# Ethernet_Connector.net
KiCad netlist of a schematic drawn in Altium Designer
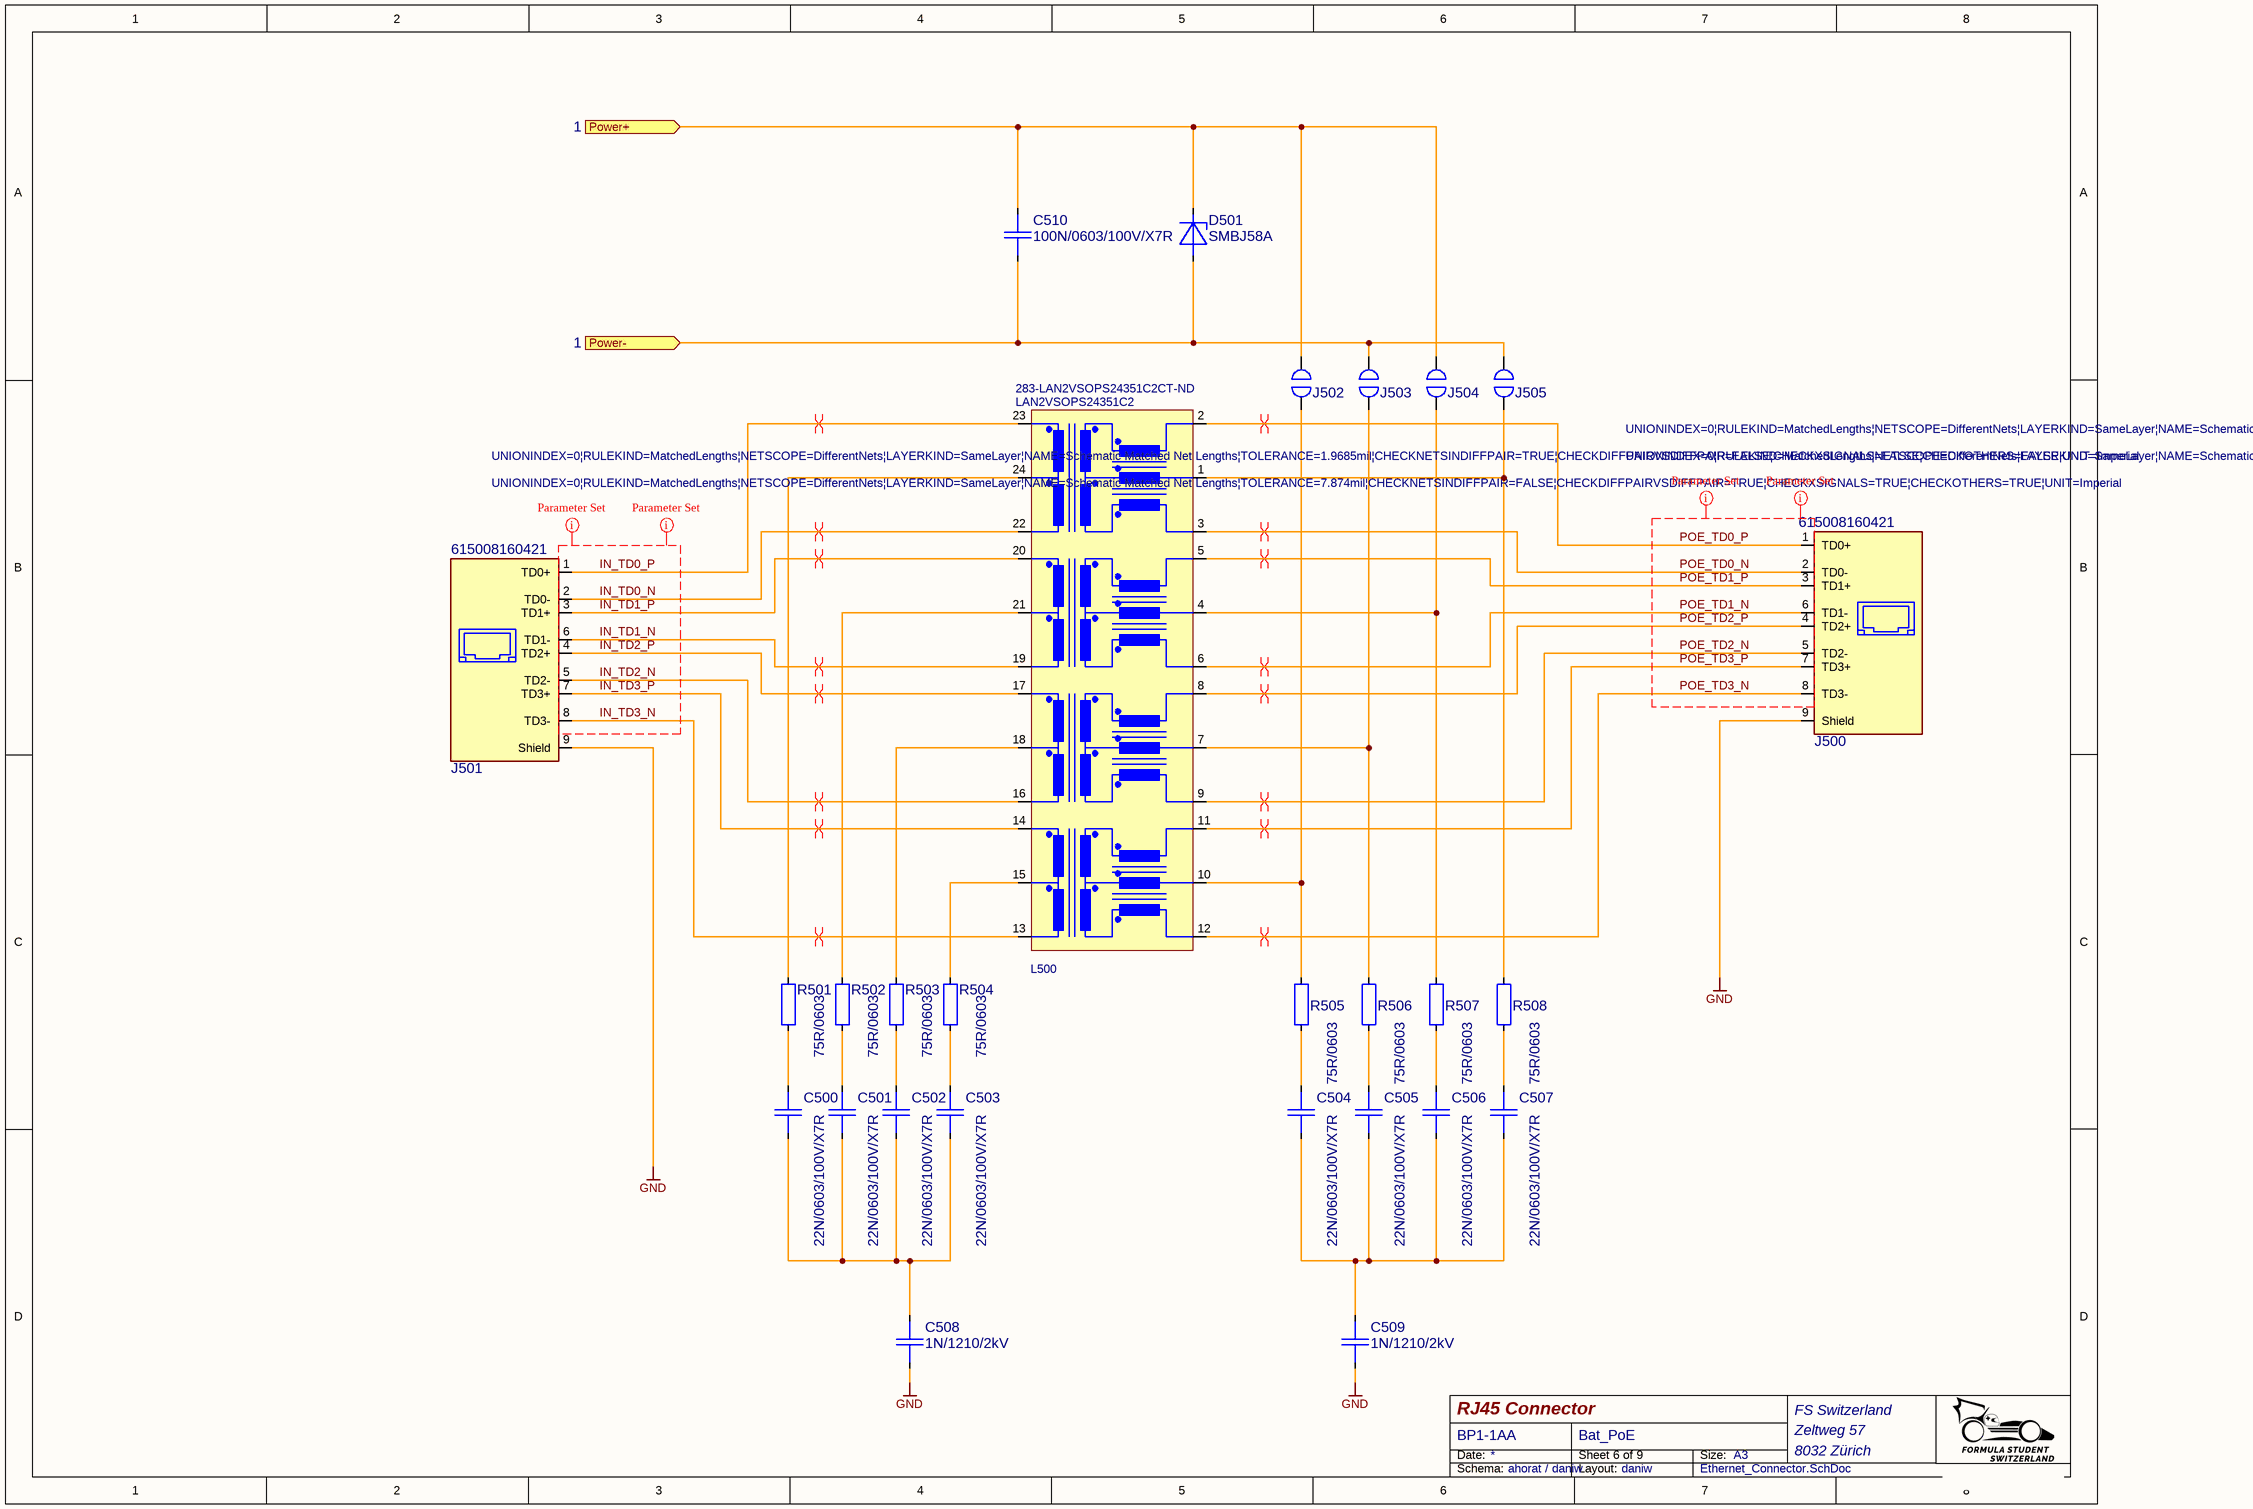
[diagram p0: Ethernet_Connector.SchDoc]

(export (version "E")
  (design (tool "Eeschema 10.0.6"))
  (components
    (comp (ref "C500")
      (value "22N/0603/100V/X7R")
      (footprint "CAP0603_X7R")
      (description "CAP SM 0603 22nF 100V X7R")
      (fields (field (name "MANUFACTURER") "GENERIC"))
      (libsource (lib "daniw_altium_lib") (part "C"))
    )
    (comp (ref "C501")
      (value "22N/0603/100V/X7R")
      (footprint "CAP0603_X7R")
      (description "CAP SM 0603 22nF 100V X7R")
      (fields (field (name "MANUFACTURER") "GENERIC"))
      (libsource (lib "daniw_altium_lib") (part "C"))
    )
    (comp (ref "C502")
      (value "22N/0603/100V/X7R")
      (footprint "CAP0603_X7R")
      (description "CAP SM 0603 22nF 100V X7R")
      (fields (field (name "MANUFACTURER") "GENERIC"))
      (libsource (lib "daniw_altium_lib") (part "C"))
    )
    (comp (ref "C503")
      (value "22N/0603/100V/X7R")
      (footprint "CAP0603_X7R")
      (description "CAP SM 0603 22nF 100V X7R")
      (fields (field (name "MANUFACTURER") "GENERIC"))
      (libsource (lib "daniw_altium_lib") (part "C"))
    )
    (comp (ref "C504")
      (value "22N/0603/100V/X7R")
      (footprint "CAP0603_X7R")
      (description "CAP SM 0603 22nF 100V X7R")
      (fields (field (name "MANUFACTURER") "GENERIC"))
      (libsource (lib "daniw_altium_lib") (part "C"))
    )
    (comp (ref "C505")
      (value "22N/0603/100V/X7R")
      (footprint "CAP0603_X7R")
      (description "CAP SM 0603 22nF 100V X7R")
      (fields (field (name "MANUFACTURER") "GENERIC"))
      (libsource (lib "daniw_altium_lib") (part "C"))
    )
    (comp (ref "C506")
      (value "22N/0603/100V/X7R")
      (footprint "CAP0603_X7R")
      (description "CAP SM 0603 22nF 100V X7R")
      (fields (field (name "MANUFACTURER") "GENERIC"))
      (libsource (lib "daniw_altium_lib") (part "C"))
    )
    (comp (ref "C507")
      (value "22N/0603/100V/X7R")
      (footprint "CAP0603_X7R")
      (description "CAP SM 0603 22nF 100V X7R")
      (fields (field (name "MANUFACTURER") "GENERIC"))
      (libsource (lib "daniw_altium_lib") (part "C"))
    )
    (comp (ref "C508")
      (value "1N/1210/2kV")
      (footprint "CAP1210_X7R")
      (description "CAP SM 1210 1nF 2kV")
      (fields (field (name "MANUFACTURER") "GENERIC"))
      (libsource (lib "daniw_altium_lib") (part "C"))
    )
    (comp (ref "C509")
      (value "1N/1210/2kV")
      (footprint "CAP1210_X7R")
      (description "CAP SM 1210 1nF 2kV")
      (fields (field (name "MANUFACTURER") "GENERIC"))
      (libsource (lib "daniw_altium_lib") (part "C"))
    )
    (comp (ref "C510")
      (value "100N/0603/100V/X7R")
      (footprint "CAP0603_X7R")
      (description "CAP SM 0603 100nF 100V X7R")
      (fields (field (name "MANUFACTURER") "GENERIC"))
      (libsource (lib "daniw_altium_lib") (part "C"))
    )
    (comp (ref "D501")
      (value "SMBJ58A")
      (footprint "DIOM5436X265")
      (description "TVS DIODE 58VWM 93.6VC DO214AA")
      (fields (field (name "MANUFACTURER") "Littelfuse Inc."))
      (libsource (lib "daniw_altium_lib") (part "D_Zener"))
    )
    (comp (ref "J500")
      (value "615008160421")
      (footprint "ETH_615008160421")
      (description "CONN MOD JACK 8P8C VERT SHIELDED")
      (fields (field (name "PART NUMBER") "ETH_THT_Vert_Schielded") (field (name "MANUFACTURER") "GENERIC"))
      (libsource (lib "daniw_altium_lib") (part "RJ-45 ETH W/O LED"))
    )
    (comp (ref "J501")
      (value "615008160421")
      (footprint "ETH_615008160421")
      (description "CONN MOD JACK 8P8C VERT SHIELDED")
      (fields (field (name "PART NUMBER") "ETH_THT_Vert_Schielded") (field (name "MANUFACTURER") "GENERIC"))
      (libsource (lib "") (part "RJ-45 ETH W/O LED_1"))
    )
    (comp (ref "J502")
      (value "Solder Jumper 2pin 0.2mm small")
      (footprint "Solder_Jumper_2pin_0.2mm_small")
      (description "Solder jumper with two pins with a spacing of 0.2mm")
      (fields
        (field (name "PART NUMBER") "Solder_Jumper_2pin_0.2mm_small")
        (field (name "MANUFACTURER") "NONE")
      )
      (libsource (lib "daniw_altium_lib") (part "SolderJumper_2"))
    )
    (comp (ref "J503")
      (value "Solder Jumper 2pin 0.2mm small")
      (footprint "Solder_Jumper_2pin_0.2mm_small")
      (description "Solder jumper with two pins with a spacing of 0.2mm")
      (fields
        (field (name "PART NUMBER") "Solder_Jumper_2pin_0.2mm_small")
        (field (name "MANUFACTURER") "NONE")
      )
      (libsource (lib "daniw_altium_lib") (part "SolderJumper_2"))
    )
    (comp (ref "J504")
      (value "Solder Jumper 2pin 0.2mm small")
      (footprint "Solder_Jumper_2pin_0.2mm_small")
      (description "Solder jumper with two pins with a spacing of 0.2mm")
      (fields
        (field (name "PART NUMBER") "Solder_Jumper_2pin_0.2mm_small")
        (field (name "MANUFACTURER") "NONE")
      )
      (libsource (lib "daniw_altium_lib") (part "SolderJumper_2"))
    )
    (comp (ref "J505")
      (value "Solder Jumper 2pin 0.2mm small")
      (footprint "Solder_Jumper_2pin_0.2mm_small")
      (description "Solder jumper with two pins with a spacing of 0.2mm")
      (fields
        (field (name "PART NUMBER") "Solder_Jumper_2pin_0.2mm_small")
        (field (name "MANUFACTURER") "NONE")
      )
      (libsource (lib "daniw_altium_lib") (part "SolderJumper_2"))
    )
    (comp (ref "L500")
      (value "LAN2VSOPS24351C2")
      (footprint "IND127P1600X620-24")
      (description "350µH LAN 1000 Base-T, Power over Ethernet (PoE) Pulswandler 1CT:1CT Oberflächenmontage")
      (fields
        (field (name "MANUFACTURER") "Eaton")
        (field (name "SUPPLIER PART NUMBER 1") "283-LAN2VSOPS24351C2CT-ND")
      )
      (libsource (lib "daniw_altium_lib") (part "Pulse_4Channel_CT"))
    )
    (comp (ref "R501")
      (value "75R/0603")
      (footprint "R0603-0.40-WW")
      (description "RES SM 0603 75R")
      (fields (field (name "MANUFACTURER") "GENERIC"))
      (libsource (lib "daniw_altium_lib") (part "R"))
    )
    (comp (ref "R502")
      (value "75R/0603")
      (footprint "R0603-0.40-WW")
      (description "RES SM 0603 75R")
      (fields (field (name "MANUFACTURER") "GENERIC"))
      (libsource (lib "daniw_altium_lib") (part "R"))
    )
    (comp (ref "R503")
      (value "75R/0603")
      (footprint "R0603-0.40-WW")
      (description "RES SM 0603 75R")
      (fields (field (name "MANUFACTURER") "GENERIC"))
      (libsource (lib "daniw_altium_lib") (part "R"))
    )
    (comp (ref "R504")
      (value "75R/0603")
      (footprint "R0603-0.40-WW")
      (description "RES SM 0603 75R")
      (fields (field (name "MANUFACTURER") "GENERIC"))
      (libsource (lib "daniw_altium_lib") (part "R"))
    )
    (comp (ref "R505")
      (value "75R/0603")
      (footprint "R0603-0.40-WW")
      (description "RES SM 0603 75R")
      (fields (field (name "MANUFACTURER") "GENERIC"))
      (libsource (lib "daniw_altium_lib") (part "R"))
    )
    (comp (ref "R506")
      (value "75R/0603")
      (footprint "R0603-0.40-WW")
      (description "RES SM 0603 75R")
      (fields (field (name "MANUFACTURER") "GENERIC"))
      (libsource (lib "daniw_altium_lib") (part "R"))
    )
    (comp (ref "R507")
      (value "75R/0603")
      (footprint "R0603-0.40-WW")
      (description "RES SM 0603 75R")
      (fields (field (name "MANUFACTURER") "GENERIC"))
      (libsource (lib "daniw_altium_lib") (part "R"))
    )
    (comp (ref "R508")
      (value "75R/0603")
      (footprint "R0603-0.40-WW")
      (description "RES SM 0603 75R")
      (fields (field (name "MANUFACTURER") "GENERIC"))
      (libsource (lib "daniw_altium_lib") (part "R"))
    )
  )
  (nets
    (net (code "1") (name "/IN_TD0_N") (class "Default")
      (node (ref "J501") (pin "2") (pinfunction "TD0-_2") (pintype "passive"))
      (node (ref "L500") (pin "22") (pintype "passive"))
    )
    (net (code "2") (name "/IN_TD0_P") (class "Default")
      (node (ref "J501") (pin "1") (pinfunction "TD0+_1") (pintype "passive"))
      (node (ref "L500") (pin "23") (pintype "passive"))
    )
    (net (code "3") (name "/IN_TD1_N") (class "Default")
      (node (ref "J501") (pin "6") (pinfunction "TD1-_6") (pintype "passive"))
      (node (ref "L500") (pin "19") (pintype "passive"))
    )
    (net (code "4") (name "/IN_TD1_P") (class "Default")
      (node (ref "J501") (pin "3") (pinfunction "TD1+_3") (pintype "passive"))
      (node (ref "L500") (pin "20") (pintype "passive"))
    )
    (net (code "5") (name "/IN_TD2_N") (class "Default")
      (node (ref "J501") (pin "5") (pinfunction "TD2-_5") (pintype "passive"))
      (node (ref "L500") (pin "16") (pintype "passive"))
    )
    (net (code "6") (name "/IN_TD2_P") (class "Default")
      (node (ref "J501") (pin "4") (pinfunction "TD2+_4") (pintype "passive"))
      (node (ref "L500") (pin "17") (pintype "passive"))
    )
    (net (code "7") (name "/IN_TD3_N") (class "Default")
      (node (ref "J501") (pin "8") (pinfunction "TD3-_8") (pintype "passive"))
      (node (ref "L500") (pin "13") (pintype "passive"))
    )
    (net (code "8") (name "/IN_TD3_P") (class "Default")
      (node (ref "J501") (pin "7") (pinfunction "TD3+_7") (pintype "passive"))
      (node (ref "L500") (pin "14") (pintype "passive"))
    )
    (net (code "9") (name "/POE_TD0_N") (class "Default")
      (node (ref "J500") (pin "2") (pinfunction "TD0-_2") (pintype "passive"))
      (node (ref "L500") (pin "3") (pintype "passive"))
    )
    (net (code "10") (name "/POE_TD0_P") (class "Default")
      (node (ref "J500") (pin "1") (pinfunction "TD0+_1") (pintype "passive"))
      (node (ref "L500") (pin "2") (pintype "passive"))
    )
    (net (code "11") (name "/POE_TD1_N") (class "Default")
      (node (ref "J500") (pin "6") (pinfunction "TD1-_6") (pintype "passive"))
      (node (ref "L500") (pin "6") (pintype "passive"))
    )
    (net (code "12") (name "/POE_TD1_P") (class "Default")
      (node (ref "J500") (pin "3") (pinfunction "TD1+_3") (pintype "passive"))
      (node (ref "L500") (pin "5") (pintype "passive"))
    )
    (net (code "13") (name "/POE_TD2_N") (class "Default")
      (node (ref "J500") (pin "5") (pinfunction "TD2-_5") (pintype "passive"))
      (node (ref "L500") (pin "9") (pintype "passive"))
    )
    (net (code "14") (name "/POE_TD2_P") (class "Default")
      (node (ref "J500") (pin "4") (pinfunction "TD2+_4") (pintype "passive"))
      (node (ref "L500") (pin "8") (pintype "passive"))
    )
    (net (code "15") (name "/POE_TD3_N") (class "Default")
      (node (ref "J500") (pin "8") (pinfunction "TD3-_8") (pintype "passive"))
      (node (ref "L500") (pin "12") (pintype "passive"))
    )
    (net (code "16") (name "/POE_TD3_P") (class "Default")
      (node (ref "J500") (pin "7") (pinfunction "TD3+_7") (pintype "passive"))
      (node (ref "L500") (pin "11") (pintype "passive"))
    )
    (net (code "17") (name "/Power+") (class "Default")
      (node (ref "C510") (pin "1") (pinfunction "1_1") (pintype "passive"))
      (node (ref "D501") (pin "1") (pinfunction "1_1") (pintype "passive"))
      (node (ref "J502") (pin "1") (pinfunction "1_1") (pintype "passive"))
      (node (ref "J504") (pin "1") (pinfunction "1_1") (pintype "passive"))
    )
    (net (code "18") (name "/Power-") (class "Default")
      (node (ref "C510") (pin "2") (pinfunction "2_2") (pintype "passive"))
      (node (ref "D501") (pin "2") (pinfunction "2_2") (pintype "passive"))
      (node (ref "J503") (pin "1") (pinfunction "1_1") (pintype "passive"))
      (node (ref "J505") (pin "1") (pinfunction "1_1") (pintype "passive"))
    )
    (net (code "19") (name "GND") (class "Default")
      (node (ref "C508") (pin "2") (pinfunction "2_2") (pintype "passive"))
      (node (ref "C509") (pin "2") (pinfunction "2_2") (pintype "passive"))
      (node (ref "J500") (pin "9") (pinfunction "Shield_9") (pintype "passive"))
      (node (ref "J501") (pin "9") (pinfunction "Shield_9") (pintype "passive"))
    )
    (net (code "20") (name "Net-(C500-Pad1)") (class "Default")
      (node (ref "C500") (pin "1") (pinfunction "1_1") (pintype "passive"))
      (node (ref "R501") (pin "2") (pinfunction "2_2") (pintype "passive"))
    )
    (net (code "21") (name "Net-(C500-Pad2)") (class "Default")
      (node (ref "C500") (pin "2") (pinfunction "2_2") (pintype "passive"))
      (node (ref "C501") (pin "2") (pinfunction "2_2") (pintype "passive"))
      (node (ref "C502") (pin "2") (pinfunction "2_2") (pintype "passive"))
      (node (ref "C503") (pin "2") (pinfunction "2_2") (pintype "passive"))
      (node (ref "C508") (pin "1") (pinfunction "1_1") (pintype "passive"))
    )
    (net (code "22") (name "Net-(C501-Pad1)") (class "Default")
      (node (ref "C501") (pin "1") (pinfunction "1_1") (pintype "passive"))
      (node (ref "R502") (pin "2") (pinfunction "2_2") (pintype "passive"))
    )
    (net (code "23") (name "Net-(C502-Pad1)") (class "Default")
      (node (ref "C502") (pin "1") (pinfunction "1_1") (pintype "passive"))
      (node (ref "R503") (pin "2") (pinfunction "2_2") (pintype "passive"))
    )
    (net (code "24") (name "Net-(C503-Pad1)") (class "Default")
      (node (ref "C503") (pin "1") (pinfunction "1_1") (pintype "passive"))
      (node (ref "R504") (pin "2") (pinfunction "2_2") (pintype "passive"))
    )
    (net (code "25") (name "Net-(C504-Pad1)") (class "Default")
      (node (ref "C504") (pin "1") (pinfunction "1_1") (pintype "passive"))
      (node (ref "R505") (pin "2") (pinfunction "2_2") (pintype "passive"))
    )
    (net (code "26") (name "Net-(C504-Pad2)") (class "Default")
      (node (ref "C504") (pin "2") (pinfunction "2_2") (pintype "passive"))
      (node (ref "C505") (pin "2") (pinfunction "2_2") (pintype "passive"))
      (node (ref "C506") (pin "2") (pinfunction "2_2") (pintype "passive"))
      (node (ref "C507") (pin "2") (pinfunction "2_2") (pintype "passive"))
      (node (ref "C509") (pin "1") (pinfunction "1_1") (pintype "passive"))
    )
    (net (code "27") (name "Net-(C505-Pad1)") (class "Default")
      (node (ref "C505") (pin "1") (pinfunction "1_1") (pintype "passive"))
      (node (ref "R506") (pin "2") (pinfunction "2_2") (pintype "passive"))
    )
    (net (code "28") (name "Net-(C506-Pad1)") (class "Default")
      (node (ref "C506") (pin "1") (pinfunction "1_1") (pintype "passive"))
      (node (ref "R507") (pin "2") (pinfunction "2_2") (pintype "passive"))
    )
    (net (code "29") (name "Net-(C507-Pad1)") (class "Default")
      (node (ref "C507") (pin "1") (pinfunction "1_1") (pintype "passive"))
      (node (ref "R508") (pin "2") (pinfunction "2_2") (pintype "passive"))
    )
    (net (code "30") (name "Net-(J502-Pad2)") (class "Default")
      (node (ref "J502") (pin "2") (pinfunction "2_2") (pintype "passive"))
      (node (ref "L500") (pin "10") (pintype "passive"))
      (node (ref "R505") (pin "1") (pinfunction "1_1") (pintype "passive"))
    )
    (net (code "31") (name "Net-(J503-Pad2)") (class "Default")
      (node (ref "J503") (pin "2") (pinfunction "2_2") (pintype "passive"))
      (node (ref "L500") (pin "7") (pintype "passive"))
      (node (ref "R506") (pin "1") (pinfunction "1_1") (pintype "passive"))
    )
    (net (code "32") (name "Net-(J504-Pad2)") (class "Default")
      (node (ref "J504") (pin "2") (pinfunction "2_2") (pintype "passive"))
      (node (ref "L500") (pin "4") (pintype "passive"))
      (node (ref "R507") (pin "1") (pinfunction "1_1") (pintype "passive"))
    )
    (net (code "33") (name "Net-(J505-Pad2)") (class "Default")
      (node (ref "J505") (pin "2") (pinfunction "2_2") (pintype "passive"))
      (node (ref "L500") (pin "1") (pintype "passive"))
      (node (ref "R508") (pin "1") (pinfunction "1_1") (pintype "passive"))
    )
    (net (code "34") (name "Net-(L500-Pad15)") (class "Default")
      (node (ref "L500") (pin "15") (pintype "passive"))
      (node (ref "R504") (pin "1") (pinfunction "1_1") (pintype "passive"))
    )
    (net (code "35") (name "Net-(L500-Pad18)") (class "Default")
      (node (ref "L500") (pin "18") (pintype "passive"))
      (node (ref "R503") (pin "1") (pinfunction "1_1") (pintype "passive"))
    )
    (net (code "36") (name "Net-(L500-Pad21)") (class "Default")
      (node (ref "L500") (pin "21") (pintype "passive"))
      (node (ref "R502") (pin "1") (pinfunction "1_1") (pintype "passive"))
    )
    (net (code "37") (name "Net-(L500-Pad24)") (class "Default")
      (node (ref "L500") (pin "24") (pintype "passive"))
      (node (ref "R501") (pin "1") (pinfunction "1_1") (pintype "passive"))
    )
  )
)
